# Contactors.net
KiCad netlist of a schematic drawn in Altium Designer
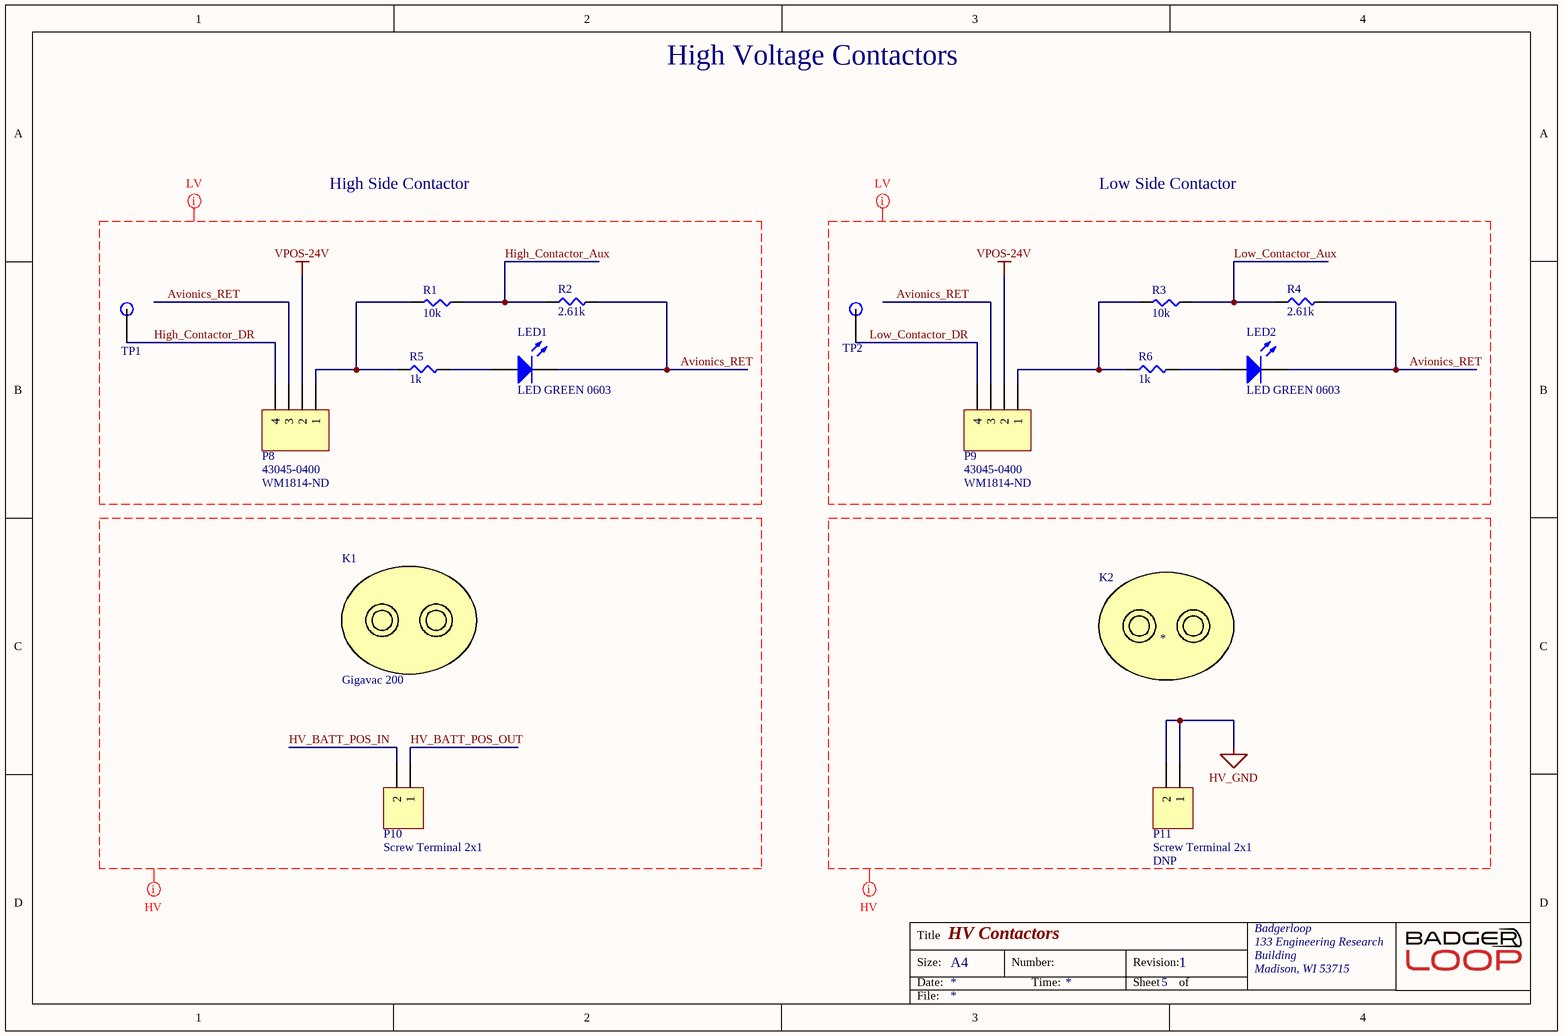
[diagram p0: Contactors.SchDoc]

(export (version "E")
  (design (tool "Eeschema 10.0.6"))
  (components
    (comp (ref "K1")
      (value "Gigavac 200")
      (footprint "Gigavac 200")
      (libsource (lib "misc") (part "Gigavac 200"))
    )
    (comp (ref "K2") (value "*") (footprint "Gigavac 200") (libsource (lib "*") (part "Gigavac 200")))
    (comp (ref "LED1")
      (value "LED GREEN 0603")
      (footprint "LED 0603 GREEN")
      (fields (field (name "MANUFACTURER") "Lite-On Inc."))
      (libsource (lib "misc") (part "LED GREEN 0603"))
    )
    (comp (ref "LED2")
      (value "LED GREEN 0603")
      (footprint "LED 0603 GREEN")
      (fields (field (name "MANUFACTURER") "Lite-On Inc."))
      (libsource (lib "misc") (part "LED GREEN 0603"))
    )
    (comp (ref "P8")
      (value "43045-0400")
      (footprint "430450400")
      (description "Male connector dual row 90° 3 mm Pole no. 2x2 Micro-Fit, 43045-0400, Molex")
      (fields (field (name "MANUFACTURER") "Molex") (field (name "SUPPLIER PART NUMBER 1") "WM1814-ND"))
      (libsource (lib "connector") (part "43045-0400"))
    )
    (comp (ref "P9")
      (value "43045-0400")
      (footprint "430450400")
      (description "Male connector dual row 90° 3 mm Pole no. 2x2 Micro-Fit, 43045-0400, Molex")
      (fields (field (name "MANUFACTURER") "Molex") (field (name "SUPPLIER PART NUMBER 1") "WM1814-ND"))
      (libsource (lib "connector") (part "43045-0400"))
    )
    (comp (ref "P10")
      (value "Screw Terminal 2x1")
      (footprint "2POS TERM BLOCK")
      (description "Screw Terminal, 2-Pin")
      (libsource (lib "connector") (part "Screw Terminal 2x1"))
    )
    (comp (ref "P11")
      (value "Screw Terminal 2x1")
      (footprint "2POS TERM BLOCK")
      (description "Screw Terminal, 2-Pin")
      (fields (field (name "DNP") "DNP"))
      (libsource (lib "connector") (part "Screw Terminal 2x1"))
    )
    (comp (ref "R1")
      (value "10k")
      (footprint "SMD-0805-RES")
      (description "RES SMD 10K OHM 5% 1/2W 0805")
      (fields (field (name "PART NUMBER") "ERJ-P06J103V") (field (name "DIGI-KEY PART NUMBER") "P10KADCT-ND"))
      (libsource (lib "resistors") (part "ERJ-P06J103V"))
    )
    (comp (ref "R2")
      (value "2.61k")
      (footprint "SMD-1206-RES")
      (description "RES SMD 2.61K OHM 1% 1/4W 1206")
      (fields
        (field (name "PART NUMBER") "ERJ-8ENF2611V")
        (field (name "DIGI-KEY PART NUMBER") "P2.61KFCT-ND")
      )
      (libsource (lib "resistors") (part "ERJ-8ENF2611V"))
    )
    (comp (ref "R3")
      (value "10k")
      (footprint "SMD-0805-RES")
      (description "RES SMD 10K OHM 5% 1/2W 0805")
      (fields (field (name "PART NUMBER") "ERJ-P06J103V") (field (name "DIGI-KEY PART NUMBER") "P10KADCT-ND"))
      (libsource (lib "resistors") (part "ERJ-P06J103V"))
    )
    (comp (ref "R4")
      (value "2.61k")
      (footprint "SMD-1206-RES")
      (description "RES SMD 2.61K OHM 1% 1/4W 1206")
      (fields
        (field (name "PART NUMBER") "ERJ-8ENF2611V")
        (field (name "DIGI-KEY PART NUMBER") "P2.61KFCT-ND")
      )
      (libsource (lib "resistors") (part "ERJ-8ENF2611V"))
    )
    (comp (ref "R5")
      (value "1k")
      (footprint "SMD-0805-RES")
      (description "RES SMD 1K OHM 1% 1/8W 0805")
      (fields
        (field (name "PART NUMBER") "ERJ-6ENF1001V")
        (field (name "DIGI-KEY PART NUMBER") "P1.00KCCT-ND")
      )
      (libsource (lib "resistors") (part "ERJ-6ENF1001V"))
    )
    (comp (ref "R6")
      (value "1k")
      (footprint "SMD-0805-RES")
      (description "RES SMD 1K OHM 1% 1/8W 0805")
      (fields
        (field (name "PART NUMBER") "ERJ-6ENF1001V")
        (field (name "DIGI-KEY PART NUMBER") "P1.00KCCT-ND")
      )
      (libsource (lib "resistors") (part "ERJ-6ENF1001V"))
    )
    (comp (ref "TP1")
      (value "TP")
      (footprint "Test Point")
      (description "SMD TEST POINT")
      (libsource (lib "misc") (part "TP"))
    )
    (comp (ref "TP2")
      (value "TP")
      (footprint "Test Point")
      (description "SMD TEST POINT")
      (libsource (lib "misc") (part "TP"))
    )
  )
  (nets
    (net (code "1") (name "/Avionics_RET") (class "Default")
      (node (ref "LED1") (pin "2") (pinfunction "K_2") (pintype "passive"))
      (node (ref "LED2") (pin "2") (pinfunction "K_2") (pintype "passive"))
      (node (ref "P8") (pin "3") (pinfunction "3_3") (pintype "passive"))
      (node (ref "P9") (pin "3") (pinfunction "3_3") (pintype "passive"))
      (node (ref "R2") (pin "2") (pinfunction "2_2") (pintype "passive"))
      (node (ref "R4") (pin "2") (pinfunction "2_2") (pintype "passive"))
    )
    (net (code "2") (name "/HV_BATT_POS_IN") (class "Default")
      (node (ref "P10") (pin "2") (pinfunction "2_2") (pintype "passive"))
    )
    (net (code "3") (name "/HV_BATT_POS_OUT") (class "Default")
      (node (ref "P10") (pin "1") (pinfunction "1_1") (pintype "passive"))
    )
    (net (code "4") (name "/High_Contactor_Aux") (class "Default")
      (node (ref "R1") (pin "1") (pinfunction "1_1") (pintype "passive"))
      (node (ref "R2") (pin "1") (pinfunction "1_1") (pintype "passive"))
    )
    (net (code "5") (name "/High_Contactor_DR") (class "Default")
      (node (ref "P8") (pin "4") (pinfunction "4_4") (pintype "passive"))
      (node (ref "TP1") (pin "1") (pinfunction "1_1") (pintype "passive"))
    )
    (net (code "6") (name "/Low_Contactor_Aux") (class "Default")
      (node (ref "R3") (pin "1") (pinfunction "1_1") (pintype "passive"))
      (node (ref "R4") (pin "1") (pinfunction "1_1") (pintype "passive"))
    )
    (net (code "7") (name "/Low_Contactor_DR") (class "Default")
      (node (ref "P9") (pin "4") (pinfunction "4_4") (pintype "passive"))
      (node (ref "TP2") (pin "1") (pinfunction "1_1") (pintype "passive"))
    )
    (net (code "8") (name "HV_GND") (class "Default")
      (node (ref "P11") (pin "1") (pinfunction "1_1") (pintype "passive"))
      (node (ref "P11") (pin "2") (pinfunction "2_2") (pintype "passive"))
    )
    (net (code "9") (name "Net-(LED1-A)") (class "Default")
      (node (ref "LED1") (pin "1") (pinfunction "A_1") (pintype "passive"))
      (node (ref "R5") (pin "2") (pinfunction "2_2") (pintype "passive"))
    )
    (net (code "10") (name "Net-(LED2-A)") (class "Default")
      (node (ref "LED2") (pin "1") (pinfunction "A_1") (pintype "passive"))
      (node (ref "R6") (pin "2") (pinfunction "2_2") (pintype "passive"))
    )
    (net (code "11") (name "Net-(P8-Pad1)") (class "Default")
      (node (ref "P8") (pin "1") (pinfunction "1_1") (pintype "passive"))
      (node (ref "R1") (pin "2") (pinfunction "2_2") (pintype "passive"))
      (node (ref "R5") (pin "1") (pinfunction "1_1") (pintype "passive"))
    )
    (net (code "12") (name "Net-(P9-Pad1)") (class "Default")
      (node (ref "P9") (pin "1") (pinfunction "1_1") (pintype "passive"))
      (node (ref "R3") (pin "2") (pinfunction "2_2") (pintype "passive"))
      (node (ref "R6") (pin "1") (pinfunction "1_1") (pintype "passive"))
    )
    (net (code "13") (name "VPOS-24V") (class "Default")
      (node (ref "P8") (pin "2") (pinfunction "2_2") (pintype "passive"))
      (node (ref "P9") (pin "2") (pinfunction "2_2") (pintype "passive"))
    )
  )
)
